# Microneedle_Patch_Panel.net
KiCad netlist of a schematic drawn in Altium Designer
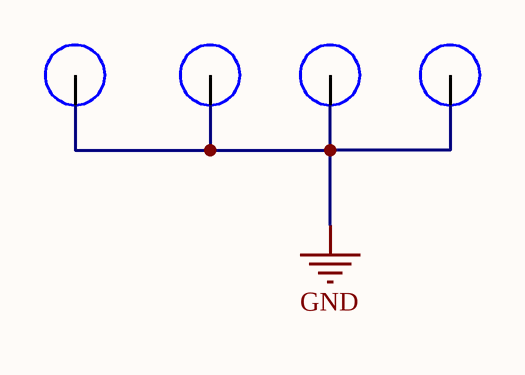
[diagram p0: Microneedle_Patch_Panel.SchDoc]

(export (version "E")
  (design (tool "Eeschema 10.0.6"))
  (components
    (comp (ref "MH1")
      (value "2 mm")
      (footprint "MH_2MM")
      (description "Mounting Hole - 2 mm")
      (libsource (lib "UHDEMG") (part "MH_2MM"))
    )
    (comp (ref "MH2")
      (value "2 mm")
      (footprint "MH_2MM")
      (description "Mounting Hole - 2 mm")
      (libsource (lib "UHDEMG") (part "MH_2MM"))
    )
    (comp (ref "MH3")
      (value "2 mm")
      (footprint "MH_2MM")
      (description "Mounting Hole - 2 mm")
      (libsource (lib "UHDEMG") (part "MH_2MM"))
    )
    (comp (ref "MH4")
      (value "2 mm")
      (footprint "MH_2MM")
      (description "Mounting Hole - 2 mm")
      (libsource (lib "UHDEMG") (part "MH_2MM"))
    )
  )
  (nets
    (net (code "1") (name "GND") (class "Default")
      (node (ref "MH1") (pin "1") (pinfunction "1_1") (pintype "passive"))
      (node (ref "MH2") (pin "1") (pinfunction "1_1") (pintype "passive"))
      (node (ref "MH3") (pin "1") (pinfunction "1_1") (pintype "passive"))
      (node (ref "MH4") (pin "1") (pinfunction "1_1") (pintype "passive"))
    )
  )
)
